# DexDrip.net
KiCad netlist of a schematic drawn in EAGLE
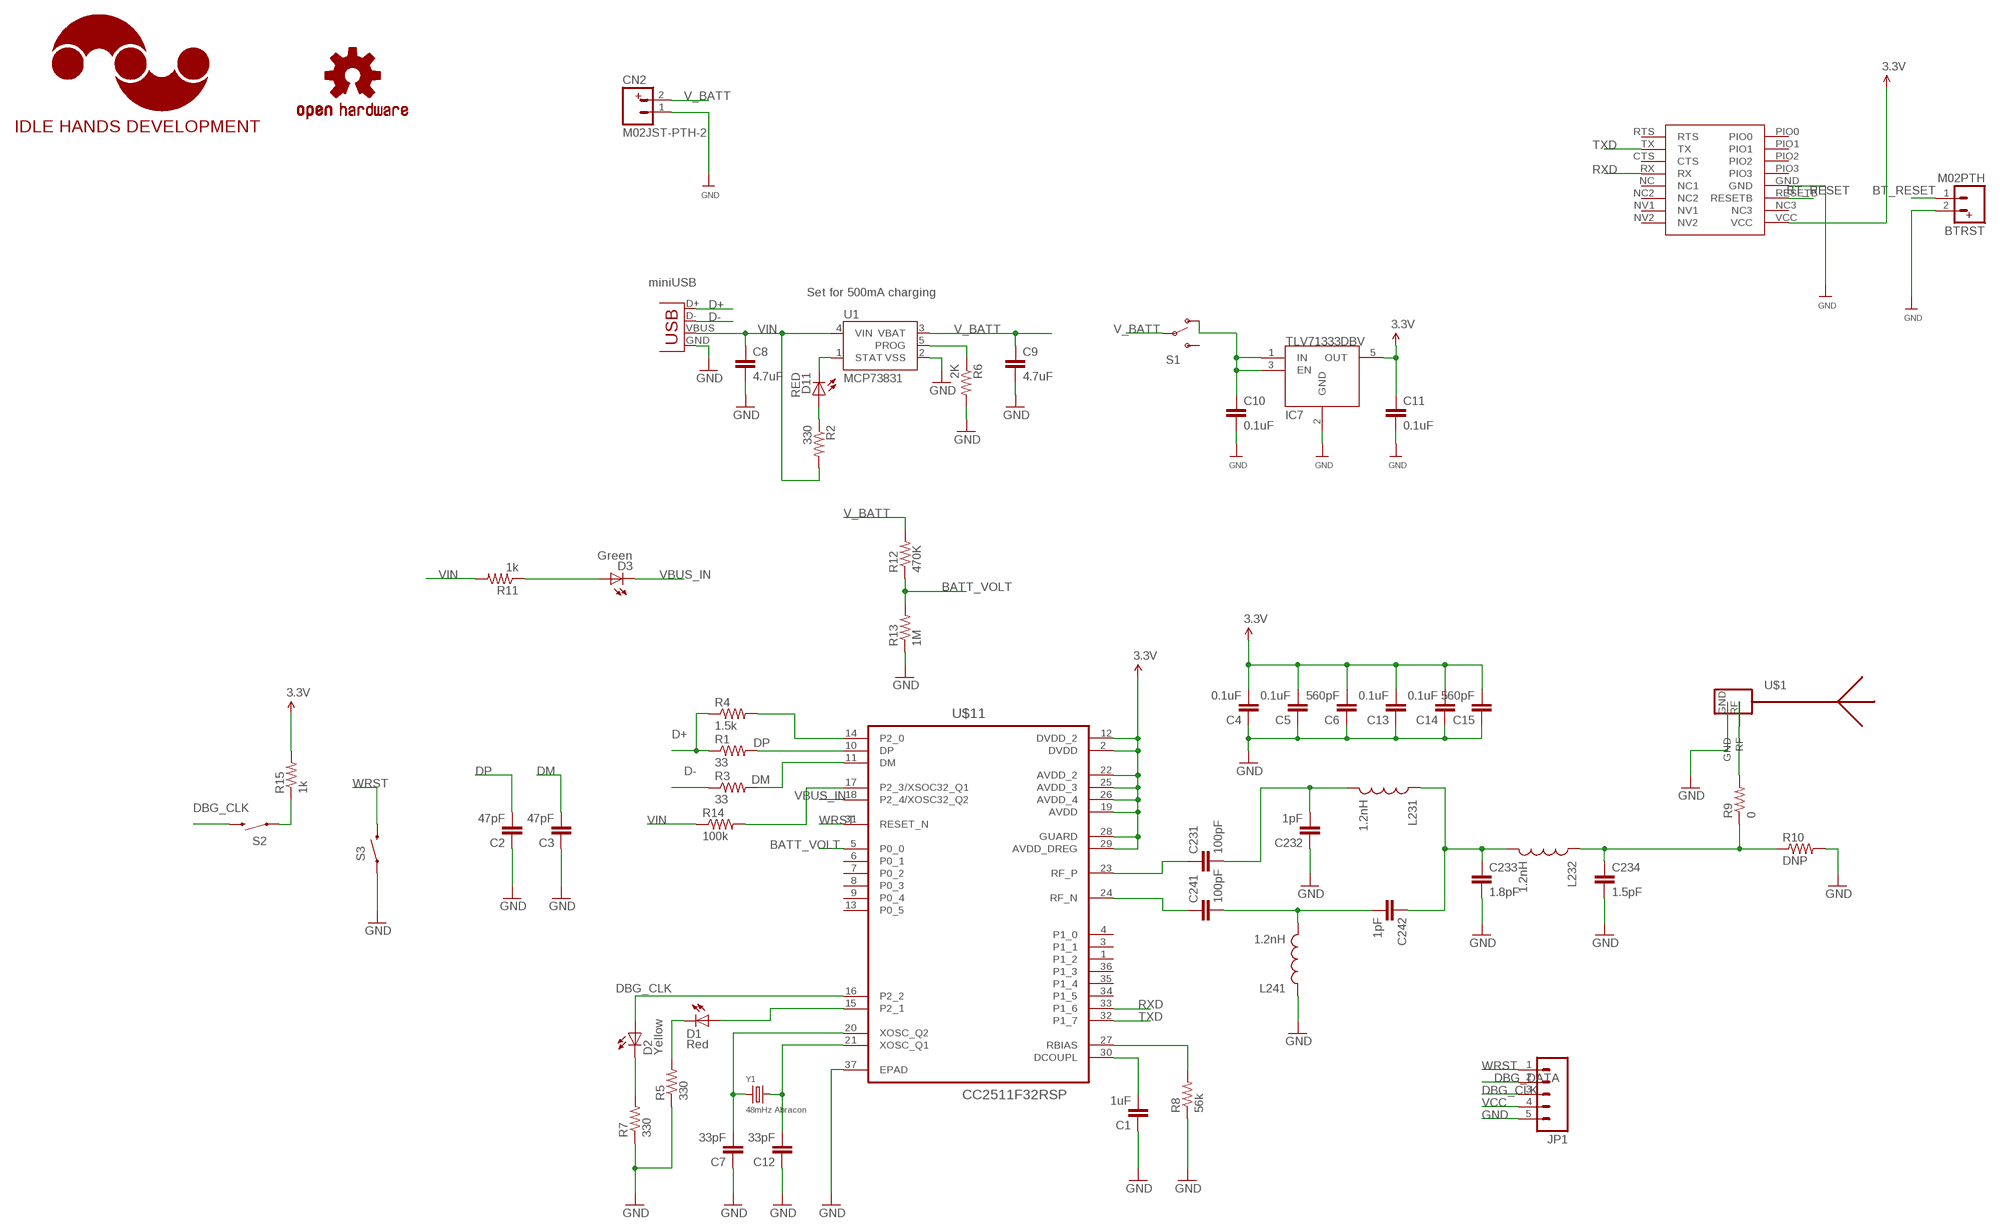
[diagram p0: schematic, sheet 1]

(export (version "E")
  (design (tool "Eeschema 10.0.6"))
  (components
    (comp (ref "BTRST")
      (value "M02PTH")
      (footprint "eagle-import:1X02")
      (libsource (lib "eagle-import") (part "M02PTH"))
    )
    (comp (ref "C1")
      (value "1uF")
      (footprint "eagle-import:0402-CAP")
      (libsource (lib "eagle-import") (part ".1UF-CER"))
    )
    (comp (ref "C2")
      (value "47pF")
      (footprint "eagle-import:0402-CAP")
      (libsource (lib "eagle-import") (part ".1UF-CER"))
    )
    (comp (ref "C3")
      (value "47pF")
      (footprint "eagle-import:0402-CAP")
      (libsource (lib "eagle-import") (part ".1UF-CER"))
    )
    (comp (ref "C4")
      (value "0.1uF")
      (footprint "eagle-import:0402-CAP")
      (libsource (lib "eagle-import") (part ".1UF-CER"))
    )
    (comp (ref "C5")
      (value "0.1uF")
      (footprint "eagle-import:0402-CAP")
      (libsource (lib "eagle-import") (part ".1UF-CER"))
    )
    (comp (ref "C6")
      (value "560pF")
      (footprint "eagle-import:0402-CAP")
      (libsource (lib "eagle-import") (part ".1UF-CER"))
    )
    (comp (ref "C7")
      (value "33pF")
      (footprint "eagle-import:0402-CAP")
      (libsource (lib "eagle-import") (part ".1UF-CER"))
    )
    (comp (ref "C8")
      (value "4.7uF")
      (footprint "eagle-import:0402-CAP")
      (libsource (lib "eagle-import") (part "CAP0402-CAP"))
    )
    (comp (ref "C9")
      (value "4.7uF")
      (footprint "eagle-import:0402-CAP")
      (libsource (lib "eagle-import") (part "CAP0402-CAP"))
    )
    (comp (ref "C10")
      (value "0.1uF")
      (footprint "eagle-import:C0402")
      (libsource (lib "eagle-import") (part "C-EUC0402"))
    )
    (comp (ref "C11")
      (value "0.1uF")
      (footprint "eagle-import:C0402")
      (libsource (lib "eagle-import") (part "C-EUC0402"))
    )
    (comp (ref "C12")
      (value "33pF")
      (footprint "eagle-import:0402-CAP")
      (libsource (lib "eagle-import") (part ".1UF-CER"))
    )
    (comp (ref "C13")
      (value "0.1uF")
      (footprint "eagle-import:0402-CAP")
      (libsource (lib "eagle-import") (part ".1UF-CER"))
    )
    (comp (ref "C14")
      (value "0.1uF")
      (footprint "eagle-import:0402-CAP")
      (libsource (lib "eagle-import") (part ".1UF-CER"))
    )
    (comp (ref "C15")
      (value "560pF")
      (footprint "eagle-import:0402-CAP")
      (libsource (lib "eagle-import") (part ".1UF-CER"))
    )
    (comp (ref "C231")
      (value "100pF")
      (footprint "eagle-import:0402-CAP")
      (libsource (lib "eagle-import") (part ".1UF-CER"))
    )
    (comp (ref "C232")
      (value "1pF")
      (footprint "eagle-import:0402-CAP")
      (libsource (lib "eagle-import") (part ".1UF-CER"))
    )
    (comp (ref "C233")
      (value "1.8pF")
      (footprint "eagle-import:0402-CAP")
      (libsource (lib "eagle-import") (part ".1UF-CER"))
    )
    (comp (ref "C234")
      (value "1.5pF")
      (footprint "eagle-import:0402-CAP")
      (libsource (lib "eagle-import") (part ".1UF-CER"))
    )
    (comp (ref "C241")
      (value "100pF")
      (footprint "eagle-import:0402-CAP")
      (libsource (lib "eagle-import") (part ".1UF-CER"))
    )
    (comp (ref "C242")
      (value "1pF")
      (footprint "eagle-import:0402-CAP")
      (libsource (lib "eagle-import") (part ".1UF-CER"))
    )
    (comp (ref "CN2")
      (value "M02JST-PTH-2")
      (footprint "eagle-import:JST-2-PTH")
      (libsource (lib "eagle-import") (part "M02JST-PTH-2"))
    )
    (comp (ref "D1")
      (value "Red")
      (footprint "eagle-import:LED-0603")
      (libsource (lib "eagle-import") (part "LED0603"))
    )
    (comp (ref "D2")
      (value "Yellow")
      (footprint "eagle-import:LED-0603")
      (libsource (lib "eagle-import") (part "LED0603"))
    )
    (comp (ref "D3")
      (value "Green")
      (footprint "eagle-import:LED-0603")
      (libsource (lib "eagle-import") (part "LED0603"))
    )
    (comp (ref "D11")
      (value "RED")
      (footprint "eagle-import:LED-0603")
      (libsource (lib "eagle-import") (part "LED0603"))
    )
    (comp (ref "IC7")
      (value "TLV71333DBV")
      (footprint "eagle-import:SOT-23-5")
      (libsource (lib "eagle-import") (part "TLV713DBV33"))
    )
    (comp (ref "JP1")
      (value "M05LOCK")
      (footprint "eagle-import:1X05_LOCK")
      (libsource (lib "eagle-import") (part "M05LOCK"))
    )
    (comp (ref "L231")
      (value "1.2nH")
      (footprint "eagle-import:C0402")
      (libsource (lib "eagle-import") (part "INDUCTOR0402"))
    )
    (comp (ref "L232")
      (value "1.2nH")
      (footprint "eagle-import:C0402")
      (libsource (lib "eagle-import") (part "INDUCTOR0402"))
    )
    (comp (ref "L241")
      (value "1.2nH")
      (footprint "eagle-import:C0402")
      (libsource (lib "eagle-import") (part "INDUCTOR0402"))
    )
    (comp (ref "LOGO1")
      (value "IDLEHANDS_LOGOS")
      (footprint "eagle-import:IHD-LOGO-S")
      (libsource (lib "eagle-import") (part "IDLEHANDS_LOGOS"))
    )
    (comp (ref "LOGO2")
      (value "OSHW-LOGOS")
      (footprint "eagle-import:OSHW-LOGO-S")
      (libsource (lib "eagle-import") (part "OSHW-LOGOS"))
    )
    (comp (ref "R1")
      (value "33")
      (footprint "eagle-import:0402-RES")
      (libsource (lib "eagle-import") (part "RESISTOR0402-RES"))
    )
    (comp (ref "R2")
      (value "330")
      (footprint "eagle-import:0402-RES")
      (libsource (lib "eagle-import") (part "RESISTOR0402-RES"))
    )
    (comp (ref "R3")
      (value "33")
      (footprint "eagle-import:0402-RES")
      (libsource (lib "eagle-import") (part "RESISTOR0402-RES"))
    )
    (comp (ref "R4")
      (value "1.5k")
      (footprint "eagle-import:0402-RES")
      (libsource (lib "eagle-import") (part "RESISTOR0402-RES"))
    )
    (comp (ref "R5")
      (value "330")
      (footprint "eagle-import:0402-RES")
      (libsource (lib "eagle-import") (part "RESISTOR0402-RES"))
    )
    (comp (ref "R6")
      (value "2K")
      (footprint "eagle-import:0402-RES")
      (libsource (lib "eagle-import") (part "RESISTOR0402-RES"))
    )
    (comp (ref "R7")
      (value "330")
      (footprint "eagle-import:0402-RES")
      (libsource (lib "eagle-import") (part "RESISTOR0402-RES"))
    )
    (comp (ref "R8")
      (value "56k")
      (footprint "eagle-import:0402-RES")
      (libsource (lib "eagle-import") (part "RESISTOR0402-RES"))
    )
    (comp (ref "R9")
      (value "0")
      (footprint "eagle-import:0402-RES")
      (libsource (lib "eagle-import") (part "RESISTOR0402-RES"))
    )
    (comp (ref "R10")
      (value "DNP")
      (footprint "eagle-import:0402-RES")
      (libsource (lib "eagle-import") (part "RESISTOR0402-RES"))
    )
    (comp (ref "R11")
      (value "1k")
      (footprint "eagle-import:0402-RES")
      (libsource (lib "eagle-import") (part "RESISTOR0402-RES"))
    )
    (comp (ref "R12")
      (value "470K")
      (footprint "eagle-import:0402-RES")
      (libsource (lib "eagle-import") (part "RESISTOR0402-RES"))
    )
    (comp (ref "R13")
      (value "1M")
      (footprint "eagle-import:0402-RES")
      (libsource (lib "eagle-import") (part "RESISTOR0402-RES"))
    )
    (comp (ref "R14")
      (value "100k")
      (footprint "eagle-import:0402-RES")
      (libsource (lib "eagle-import") (part "RESISTOR0402-RES"))
    )
    (comp (ref "R15")
      (value "1k")
      (footprint "eagle-import:0402-RES")
      (libsource (lib "eagle-import") (part "RESISTOR0402-RES"))
    )
    (comp (ref "S1")
      (value "SWITCH-SPDT-SMD-A")
      (footprint "eagle-import:SWITCH-SPST-SMD-A")
      (libsource (lib "eagle-import") (part "SWITCH-SPDT-SMD-A"))
    )
    (comp (ref "S2")
      (value "SWITCH-MOMENTARY-2-SMD-1101NE")
      (footprint "eagle-import:TACTILE-SWITCH-1101NE")
      (libsource (lib "eagle-import") (part "SWITCH-MOMENTARY-2-SMD-1101NE"))
    )
    (comp (ref "S3")
      (value "SWITCH-MOMENTARY-2-SMD-1101NE")
      (footprint "eagle-import:TACTILE-SWITCH-1101NE")
      (libsource (lib "eagle-import") (part "SWITCH-MOMENTARY-2-SMD-1101NE"))
    )
    (comp (ref "U$1")
      (value "ANTENNA_1LEFT")
      (footprint "eagle-import:SWRA117D_LEFT")
      (libsource (lib "eagle-import") (part "ANTENNA_1LEFT"))
    )
    (comp (ref "U$2")
      (value "BT_HM11")
      (footprint "eagle-import:HM11")
      (libsource (lib "eagle-import") (part "BT_HM11"))
    )
    (comp (ref "U$11")
      (value "CC2511F32RSP")
      (footprint "eagle-import:QFN50P600X600X90-37N")
      (libsource (lib "eagle-import") (part "CC2511F32RSP"))
    )
    (comp (ref "U1")
      (value "MCP73831")
      (footprint "eagle-import:SOT23-5")
      (libsource (lib "eagle-import") (part "MCP73831"))
    )
    (comp (ref "X1")
      (value "Micro USB")
      (footprint "eagle-import:USB-MICROB")
      (libsource (lib "eagle-import") (part "USB-MICROB"))
    )
    (comp (ref "Y1")
      (value "48mHz Abracon")
      (footprint "eagle-import:3.2X2.5MM")
      (libsource (lib "eagle-import") (part "CRYSTAL.3.2X2.5MM"))
    )
  )
  (nets
    (net (code "1") (name "/BATT_VOLT") (class "Default")
      (node (ref "R12") (pin "1") (pinfunction "1_1") (pintype "passive"))
      (node (ref "R13") (pin "2") (pinfunction "2_2") (pintype "passive"))
      (node (ref "U$11") (pin "5") (pinfunction "P0_0_5") (pintype "bidirectional"))
    )
    (net (code "2") (name "/BT_RESET") (class "Default")
      (node (ref "BTRST") (pin "1") (pinfunction "1_1") (pintype "passive"))
      (node (ref "U$2") (pin "RESETB") (pinfunction "RESETB_RESETB") (pintype "bidirectional"))
    )
    (net (code "3") (name "/D+") (class "Default")
      (node (ref "R1") (pin "1") (pinfunction "1_1") (pintype "passive"))
      (node (ref "R4") (pin "1") (pinfunction "1_1") (pintype "passive"))
      (node (ref "X1") (pin "D+") (pinfunction "D+_D+") (pintype "bidirectional"))
    )
    (net (code "4") (name "/D-") (class "Default")
      (node (ref "R3") (pin "1") (pinfunction "1_1") (pintype "passive"))
      (node (ref "X1") (pin "D-") (pinfunction "D-_D-") (pintype "bidirectional"))
    )
    (net (code "5") (name "/DBG_CLK") (class "Default")
      (node (ref "D2") (pin "A") (pinfunction "A_A") (pintype "passive"))
      (node (ref "JP1") (pin "3") (pinfunction "3_3") (pintype "passive"))
      (node (ref "S2") (pin "P$2") (pinfunction "2_P$2") (pintype "passive"))
      (node (ref "U$11") (pin "16") (pinfunction "P2_2_16") (pintype "bidirectional"))
    )
    (net (code "6") (name "/DBG_DATA") (class "Default")
      (node (ref "D1") (pin "A") (pinfunction "A_A") (pintype "passive"))
      (node (ref "JP1") (pin "2") (pinfunction "2_2") (pintype "passive"))
      (node (ref "U$11") (pin "15") (pinfunction "P2_1_15") (pintype "bidirectional"))
    )
    (net (code "7") (name "/DM") (class "Default")
      (node (ref "C3") (pin "2") (pinfunction "2_2") (pintype "passive"))
      (node (ref "R3") (pin "2") (pinfunction "2_2") (pintype "passive"))
      (node (ref "U$11") (pin "11") (pinfunction "DM_11") (pintype "bidirectional"))
    )
    (net (code "8") (name "/DP") (class "Default")
      (node (ref "C2") (pin "2") (pinfunction "2_2") (pintype "passive"))
      (node (ref "R1") (pin "2") (pinfunction "2_2") (pintype "passive"))
      (node (ref "U$11") (pin "10") (pinfunction "DP_10") (pintype "bidirectional"))
    )
    (net (code "9") (name "/RXD") (class "Default")
      (node (ref "U$11") (pin "33") (pinfunction "P1_6_33") (pintype "bidirectional"))
      (node (ref "U$2") (pin "RX") (pinfunction "RX_RX") (pintype "bidirectional"))
    )
    (net (code "10") (name "/TXD") (class "Default")
      (node (ref "U$11") (pin "32") (pinfunction "P1_7_32") (pintype "bidirectional"))
      (node (ref "U$2") (pin "TX") (pinfunction "TX_TX") (pintype "bidirectional"))
    )
    (net (code "11") (name "/VBUS_IN") (class "Default")
      (node (ref "D3") (pin "C") (pinfunction "C_C") (pintype "passive"))
      (node (ref "U$11") (pin "18") (pinfunction "P2_4/XOSC32_Q2_18") (pintype "power_in"))
    )
    (net (code "12") (name "/VIN") (class "Default")
      (node (ref "C8") (pin "1") (pinfunction "1_1") (pintype "passive"))
      (node (ref "R11") (pin "2") (pinfunction "2_2") (pintype "passive"))
      (node (ref "R14") (pin "1") (pinfunction "1_1") (pintype "passive"))
      (node (ref "R2") (pin "2") (pinfunction "2_2") (pintype "passive"))
      (node (ref "U1") (pin "4") (pinfunction "VIN_4") (pintype "power_in"))
      (node (ref "X1") (pin "VBUS") (pinfunction "VBUS_VBUS") (pintype "bidirectional"))
    )
    (net (code "13") (name "/V_BATT") (class "Default")
      (node (ref "C9") (pin "1") (pinfunction "1_1") (pintype "passive"))
      (node (ref "CN2") (pin "2") (pinfunction "2_2") (pintype "passive"))
      (node (ref "R12") (pin "2") (pinfunction "2_2") (pintype "passive"))
      (node (ref "S1") (pin "2") (pinfunction "P_2") (pintype "passive"))
      (node (ref "U1") (pin "3") (pinfunction "VBAT_3") (pintype "power_in"))
    )
    (net (code "14") (name "/WRST") (class "Default")
      (node (ref "JP1") (pin "1") (pinfunction "1_1") (pintype "passive"))
      (node (ref "S3") (pin "P$2") (pinfunction "2_P$2") (pintype "passive"))
      (node (ref "U$11") (pin "31") (pinfunction "RESET_N_31") (pintype "input"))
    )
    (net (code "15") (name "3.3V") (class "Default")
      (node (ref "C11") (pin "1") (pinfunction "1_1") (pintype "passive"))
      (node (ref "C13") (pin "2") (pinfunction "2_2") (pintype "passive"))
      (node (ref "C14") (pin "2") (pinfunction "2_2") (pintype "passive"))
      (node (ref "C15") (pin "2") (pinfunction "2_2") (pintype "passive"))
      (node (ref "C4") (pin "2") (pinfunction "2_2") (pintype "passive"))
      (node (ref "C5") (pin "2") (pinfunction "2_2") (pintype "passive"))
      (node (ref "C6") (pin "2") (pinfunction "2_2") (pintype "passive"))
      (node (ref "IC7") (pin "5") (pinfunction "OUT_5") (pintype "power_in"))
      (node (ref "JP1") (pin "4") (pinfunction "4_4") (pintype "passive"))
      (node (ref "R15") (pin "2") (pinfunction "2_2") (pintype "passive"))
      (node (ref "U$11") (pin "12") (pinfunction "DVDD_2_12") (pintype "power_in"))
      (node (ref "U$11") (pin "19") (pinfunction "AVDD_19") (pintype "power_in"))
      (node (ref "U$11") (pin "2") (pinfunction "DVDD_2") (pintype "power_in"))
      (node (ref "U$11") (pin "22") (pinfunction "AVDD_2_22") (pintype "power_in"))
      (node (ref "U$11") (pin "25") (pinfunction "AVDD_3_25") (pintype "power_in"))
      (node (ref "U$11") (pin "26") (pinfunction "AVDD_4_26") (pintype "power_in"))
      (node (ref "U$11") (pin "28") (pinfunction "GUARD_28") (pintype "power_in"))
      (node (ref "U$11") (pin "29") (pinfunction "AVDD_DREG_29") (pintype "power_in"))
      (node (ref "U$2") (pin "VCC") (pinfunction "VCC_VCC") (pintype "power_in"))
    )
    (net (code "16") (name "GND") (class "Default")
      (node (ref "BTRST") (pin "2") (pinfunction "2_2") (pintype "passive"))
      (node (ref "C1") (pin "1") (pinfunction "1_1") (pintype "passive"))
      (node (ref "C10") (pin "2") (pinfunction "2_2") (pintype "passive"))
      (node (ref "C11") (pin "2") (pinfunction "2_2") (pintype "passive"))
      (node (ref "C12") (pin "1") (pinfunction "1_1") (pintype "passive"))
      (node (ref "C13") (pin "1") (pinfunction "1_1") (pintype "passive"))
      (node (ref "C14") (pin "1") (pinfunction "1_1") (pintype "passive"))
      (node (ref "C15") (pin "1") (pinfunction "1_1") (pintype "passive"))
      (node (ref "C2") (pin "1") (pinfunction "1_1") (pintype "passive"))
      (node (ref "C232") (pin "1") (pinfunction "1_1") (pintype "passive"))
      (node (ref "C233") (pin "2") (pinfunction "2_2") (pintype "passive"))
      (node (ref "C234") (pin "2") (pinfunction "2_2") (pintype "passive"))
      (node (ref "C3") (pin "1") (pinfunction "1_1") (pintype "passive"))
      (node (ref "C4") (pin "1") (pinfunction "1_1") (pintype "passive"))
      (node (ref "C5") (pin "1") (pinfunction "1_1") (pintype "passive"))
      (node (ref "C6") (pin "1") (pinfunction "1_1") (pintype "passive"))
      (node (ref "C7") (pin "1") (pinfunction "1_1") (pintype "passive"))
      (node (ref "C8") (pin "2") (pinfunction "2_2") (pintype "passive"))
      (node (ref "C9") (pin "2") (pinfunction "2_2") (pintype "passive"))
      (node (ref "CN2") (pin "1") (pinfunction "1_1") (pintype "passive"))
      (node (ref "IC7") (pin "2") (pinfunction "GND_2") (pintype "power_in"))
      (node (ref "JP1") (pin "5") (pinfunction "5_5") (pintype "passive"))
      (node (ref "L241") (pin "1") (pinfunction "1_1") (pintype "passive"))
      (node (ref "R10") (pin "2") (pinfunction "2_2") (pintype "passive"))
      (node (ref "R13") (pin "1") (pinfunction "1_1") (pintype "passive"))
      (node (ref "R5") (pin "1") (pinfunction "1_1") (pintype "passive"))
      (node (ref "R6") (pin "2") (pinfunction "2_2") (pintype "passive"))
      (node (ref "R7") (pin "1") (pinfunction "1_1") (pintype "passive"))
      (node (ref "R8") (pin "1") (pinfunction "1_1") (pintype "passive"))
      (node (ref "S3") (pin "P$1") (pinfunction "1_P$1") (pintype "passive"))
      (node (ref "U$1") (pin "GND") (pinfunction "GND_GND") (pintype "passive"))
      (node (ref "U$11") (pin "37") (pinfunction "EPAD_37") (pintype "passive"))
      (node (ref "U$2") (pin "GND") (pinfunction "GND_GND") (pintype "power_in"))
      (node (ref "U1") (pin "2") (pinfunction "VSS_2") (pintype "power_in"))
      (node (ref "X1") (pin "GND") (pinfunction "GND_GND") (pintype "bidirectional"))
    )
    (net (code "17") (name "Net-(C231-Pad2)") (class "Default")
      (node (ref "C231") (pin "2") (pinfunction "2_2") (pintype "passive"))
      (node (ref "C232") (pin "2") (pinfunction "2_2") (pintype "passive"))
      (node (ref "L231") (pin "2") (pinfunction "2_2") (pintype "passive"))
    )
    (net (code "18") (name "Net-(C233-Pad1)") (class "Default")
      (node (ref "C233") (pin "1") (pinfunction "1_1") (pintype "passive"))
      (node (ref "C242") (pin "1") (pinfunction "1_1") (pintype "passive"))
      (node (ref "L231") (pin "1") (pinfunction "1_1") (pintype "passive"))
      (node (ref "L232") (pin "2") (pinfunction "2_2") (pintype "passive"))
    )
    (net (code "19") (name "Net-(C234-Pad1)") (class "Default")
      (node (ref "C234") (pin "1") (pinfunction "1_1") (pintype "passive"))
      (node (ref "L232") (pin "1") (pinfunction "1_1") (pintype "passive"))
      (node (ref "R10") (pin "1") (pinfunction "1_1") (pintype "passive"))
      (node (ref "R9") (pin "1") (pinfunction "1_1") (pintype "passive"))
    )
    (net (code "20") (name "Net-(C241-Pad2)") (class "Default")
      (node (ref "C241") (pin "2") (pinfunction "2_2") (pintype "passive"))
      (node (ref "C242") (pin "2") (pinfunction "2_2") (pintype "passive"))
      (node (ref "L241") (pin "2") (pinfunction "2_2") (pintype "passive"))
    )
    (net (code "21") (name "Net-(D1-PadC)") (class "Default")
      (node (ref "D1") (pin "C") (pinfunction "C_C") (pintype "passive"))
      (node (ref "R5") (pin "2") (pinfunction "2_2") (pintype "passive"))
    )
    (net (code "22") (name "Net-(D2-PadC)") (class "Default")
      (node (ref "D2") (pin "C") (pinfunction "C_C") (pintype "passive"))
      (node (ref "R7") (pin "2") (pinfunction "2_2") (pintype "passive"))
    )
    (net (code "23") (name "Net-(D3-PadA)") (class "Default")
      (node (ref "D3") (pin "A") (pinfunction "A_A") (pintype "passive"))
      (node (ref "R11") (pin "1") (pinfunction "1_1") (pintype "passive"))
    )
    (net (code "24") (name "Net-(D11-PadA)") (class "Default")
      (node (ref "D11") (pin "A") (pinfunction "A_A") (pintype "passive"))
      (node (ref "R2") (pin "1") (pinfunction "1_1") (pintype "passive"))
    )
    (net (code "25") (name "Net-(IC7-EN)") (class "Default")
      (node (ref "C10") (pin "1") (pinfunction "1_1") (pintype "passive"))
      (node (ref "IC7") (pin "1") (pinfunction "IN_1") (pintype "power_in"))
      (node (ref "IC7") (pin "3") (pinfunction "EN_3") (pintype "input"))
      (node (ref "S1") (pin "1") (pinfunction "O_1") (pintype "passive"))
    )
    (net (code "26") (name "Net-(R9-Pad2)") (class "Default")
      (node (ref "R9") (pin "2") (pinfunction "2_2") (pintype "passive"))
      (node (ref "U$1") (pin "RF") (pinfunction "RF_RF") (pintype "bidirectional"))
    )
    (net (code "27") (name "Net-(S2-1)") (class "Default")
      (node (ref "R15") (pin "1") (pinfunction "1_1") (pintype "passive"))
      (node (ref "S2") (pin "P$1") (pinfunction "1_P$1") (pintype "passive"))
    )
    (net (code "28") (name "Net-(U$11-DCOUPL)") (class "Default")
      (node (ref "C1") (pin "2") (pinfunction "2_2") (pintype "passive"))
      (node (ref "U$11") (pin "30") (pinfunction "DCOUPL_30") (pintype "input"))
    )
    (net (code "29") (name "Net-(U$11-P2_0)") (class "Default")
      (node (ref "R4") (pin "2") (pinfunction "2_2") (pintype "passive"))
      (node (ref "U$11") (pin "14") (pinfunction "P2_0_14") (pintype "bidirectional"))
    )
    (net (code "30") (name "Net-(U$11-P2_3{slash}XSOC32_Q1)") (class "Default")
      (node (ref "R14") (pin "2") (pinfunction "2_2") (pintype "passive"))
      (node (ref "U$11") (pin "17") (pinfunction "P2_3/XSOC32_Q1_17") (pintype "bidirectional"))
    )
    (net (code "31") (name "Net-(U$11-RBIAS)") (class "Default")
      (node (ref "R8") (pin "2") (pinfunction "2_2") (pintype "passive"))
      (node (ref "U$11") (pin "27") (pinfunction "RBIAS_27") (pintype "input"))
    )
    (net (code "32") (name "Net-(U$11-RF_N)") (class "Default")
      (node (ref "C241") (pin "1") (pinfunction "1_1") (pintype "passive"))
      (node (ref "U$11") (pin "24") (pinfunction "RF_N_24") (pintype "input"))
    )
    (net (code "33") (name "Net-(U$11-RF_P)") (class "Default")
      (node (ref "C231") (pin "1") (pinfunction "1_1") (pintype "passive"))
      (node (ref "U$11") (pin "23") (pinfunction "RF_P_23") (pintype "input"))
    )
    (net (code "34") (name "Net-(U$11-XOSC_Q1)") (class "Default")
      (node (ref "C12") (pin "2") (pinfunction "2_2") (pintype "passive"))
      (node (ref "U$11") (pin "21") (pinfunction "XOSC_Q1_21") (pintype "bidirectional"))
      (node (ref "Y1") (pin "3") (pinfunction "2_3") (pintype "passive"))
    )
    (net (code "35") (name "Net-(U$11-XOSC_Q2)") (class "Default")
      (node (ref "C7") (pin "2") (pinfunction "2_2") (pintype "passive"))
      (node (ref "U$11") (pin "20") (pinfunction "XOSC_Q2_20") (pintype "bidirectional"))
      (node (ref "Y1") (pin "1") (pinfunction "1_1") (pintype "passive"))
    )
    (net (code "36") (name "Net-(U1-PROG)") (class "Default")
      (node (ref "R6") (pin "1") (pinfunction "1_1") (pintype "passive"))
      (node (ref "U1") (pin "5") (pinfunction "PROG_5") (pintype "input"))
    )
    (net (code "37") (name "Net-(U1-STAT)") (class "Default")
      (node (ref "D11") (pin "C") (pinfunction "C_C") (pintype "passive"))
      (node (ref "U1") (pin "1") (pinfunction "STAT_1") (pintype "output"))
    )
    (net (code "38") (name "unconnected-(S1-S-Pad3)") (class "Default")
      (node (ref "S1") (pin "3") (pinfunction "S_3") (pintype "passive"))
    )
    (net (code "39") (name "unconnected-(U$2-NC1-PadNC)") (class "Default")
      (node (ref "U$2") (pin "NC") (pinfunction "NC1_NC") (pintype "no_connect"))
    )
    (net (code "40") (name "unconnected-(U$2-PadCTS)") (class "Default")
      (node (ref "U$2") (pin "CTS") (pinfunction "CTS_CTS") (pintype "bidirectional"))
    )
    (net (code "41") (name "unconnected-(U$2-PadNC2)") (class "Default")
      (node (ref "U$2") (pin "NC2") (pinfunction "NC2_NC2") (pintype "no_connect"))
    )
    (net (code "42") (name "unconnected-(U$2-PadNC3)") (class "Default")
      (node (ref "U$2") (pin "NC3") (pinfunction "NC3_NC3") (pintype "no_connect"))
    )
    (net (code "43") (name "unconnected-(U$2-PadNV1)") (class "Default")
      (node (ref "U$2") (pin "NV1") (pinfunction "NV1_NV1") (pintype "no_connect"))
    )
    (net (code "44") (name "unconnected-(U$2-PadNV2)") (class "Default")
      (node (ref "U$2") (pin "NV2") (pinfunction "NV2_NV2") (pintype "no_connect"))
    )
    (net (code "45") (name "unconnected-(U$2-PadPIO0)") (class "Default")
      (node (ref "U$2") (pin "PIO0") (pinfunction "PIO0_PIO0") (pintype "bidirectional"))
    )
    (net (code "46") (name "unconnected-(U$2-PadPIO1)") (class "Default")
      (node (ref "U$2") (pin "PIO1") (pinfunction "PIO1_PIO1") (pintype "bidirectional"))
    )
    (net (code "47") (name "unconnected-(U$2-PadPIO2)") (class "Default")
      (node (ref "U$2") (pin "PIO2") (pinfunction "PIO2_PIO2") (pintype "bidirectional"))
    )
    (net (code "48") (name "unconnected-(U$2-PadPIO3)") (class "Default")
      (node (ref "U$2") (pin "PIO3") (pinfunction "PIO3_PIO3") (pintype "bidirectional"))
    )
    (net (code "49") (name "unconnected-(U$2-PadRTS)") (class "Default")
      (node (ref "U$2") (pin "RTS") (pinfunction "RTS_RTS") (pintype "bidirectional"))
    )
    (net (code "50") (name "unconnected-(U$11-P0_1-Pad6)") (class "Default")
      (node (ref "U$11") (pin "6") (pinfunction "P0_1_6") (pintype "bidirectional"))
    )
    (net (code "51") (name "unconnected-(U$11-P0_2-Pad7)") (class "Default")
      (node (ref "U$11") (pin "7") (pinfunction "P0_2_7") (pintype "bidirectional"))
    )
    (net (code "52") (name "unconnected-(U$11-P0_3-Pad8)") (class "Default")
      (node (ref "U$11") (pin "8") (pinfunction "P0_3_8") (pintype "bidirectional"))
    )
    (net (code "53") (name "unconnected-(U$11-P0_4-Pad9)") (class "Default")
      (node (ref "U$11") (pin "9") (pinfunction "P0_4_9") (pintype "bidirectional"))
    )
    (net (code "54") (name "unconnected-(U$11-P0_5-Pad13)") (class "Default")
      (node (ref "U$11") (pin "13") (pinfunction "P0_5_13") (pintype "bidirectional"))
    )
    (net (code "55") (name "unconnected-(U$11-P1_0-Pad4)") (class "Default")
      (node (ref "U$11") (pin "4") (pinfunction "P1_0_4") (pintype "bidirectional"))
    )
    (net (code "56") (name "unconnected-(U$11-P1_1-Pad3)") (class "Default")
      (node (ref "U$11") (pin "3") (pinfunction "P1_1_3") (pintype "bidirectional"))
    )
    (net (code "57") (name "unconnected-(U$11-P1_2-Pad1)") (class "Default")
      (node (ref "U$11") (pin "1") (pinfunction "P1_2_1") (pintype "bidirectional"))
    )
    (net (code "58") (name "unconnected-(U$11-P1_3-Pad36)") (class "Default")
      (node (ref "U$11") (pin "36") (pinfunction "P1_3_36") (pintype "bidirectional"))
    )
    (net (code "59") (name "unconnected-(U$11-P1_4-Pad35)") (class "Default")
      (node (ref "U$11") (pin "35") (pinfunction "P1_4_35") (pintype "bidirectional"))
    )
    (net (code "60") (name "unconnected-(U$11-P1_5-Pad34)") (class "Default")
      (node (ref "U$11") (pin "34") (pinfunction "P1_5_34") (pintype "bidirectional"))
    )
  )
)
